# CH32H416RDU6-R0.net
KiCad netlist of a schematic drawn in Altium Designer
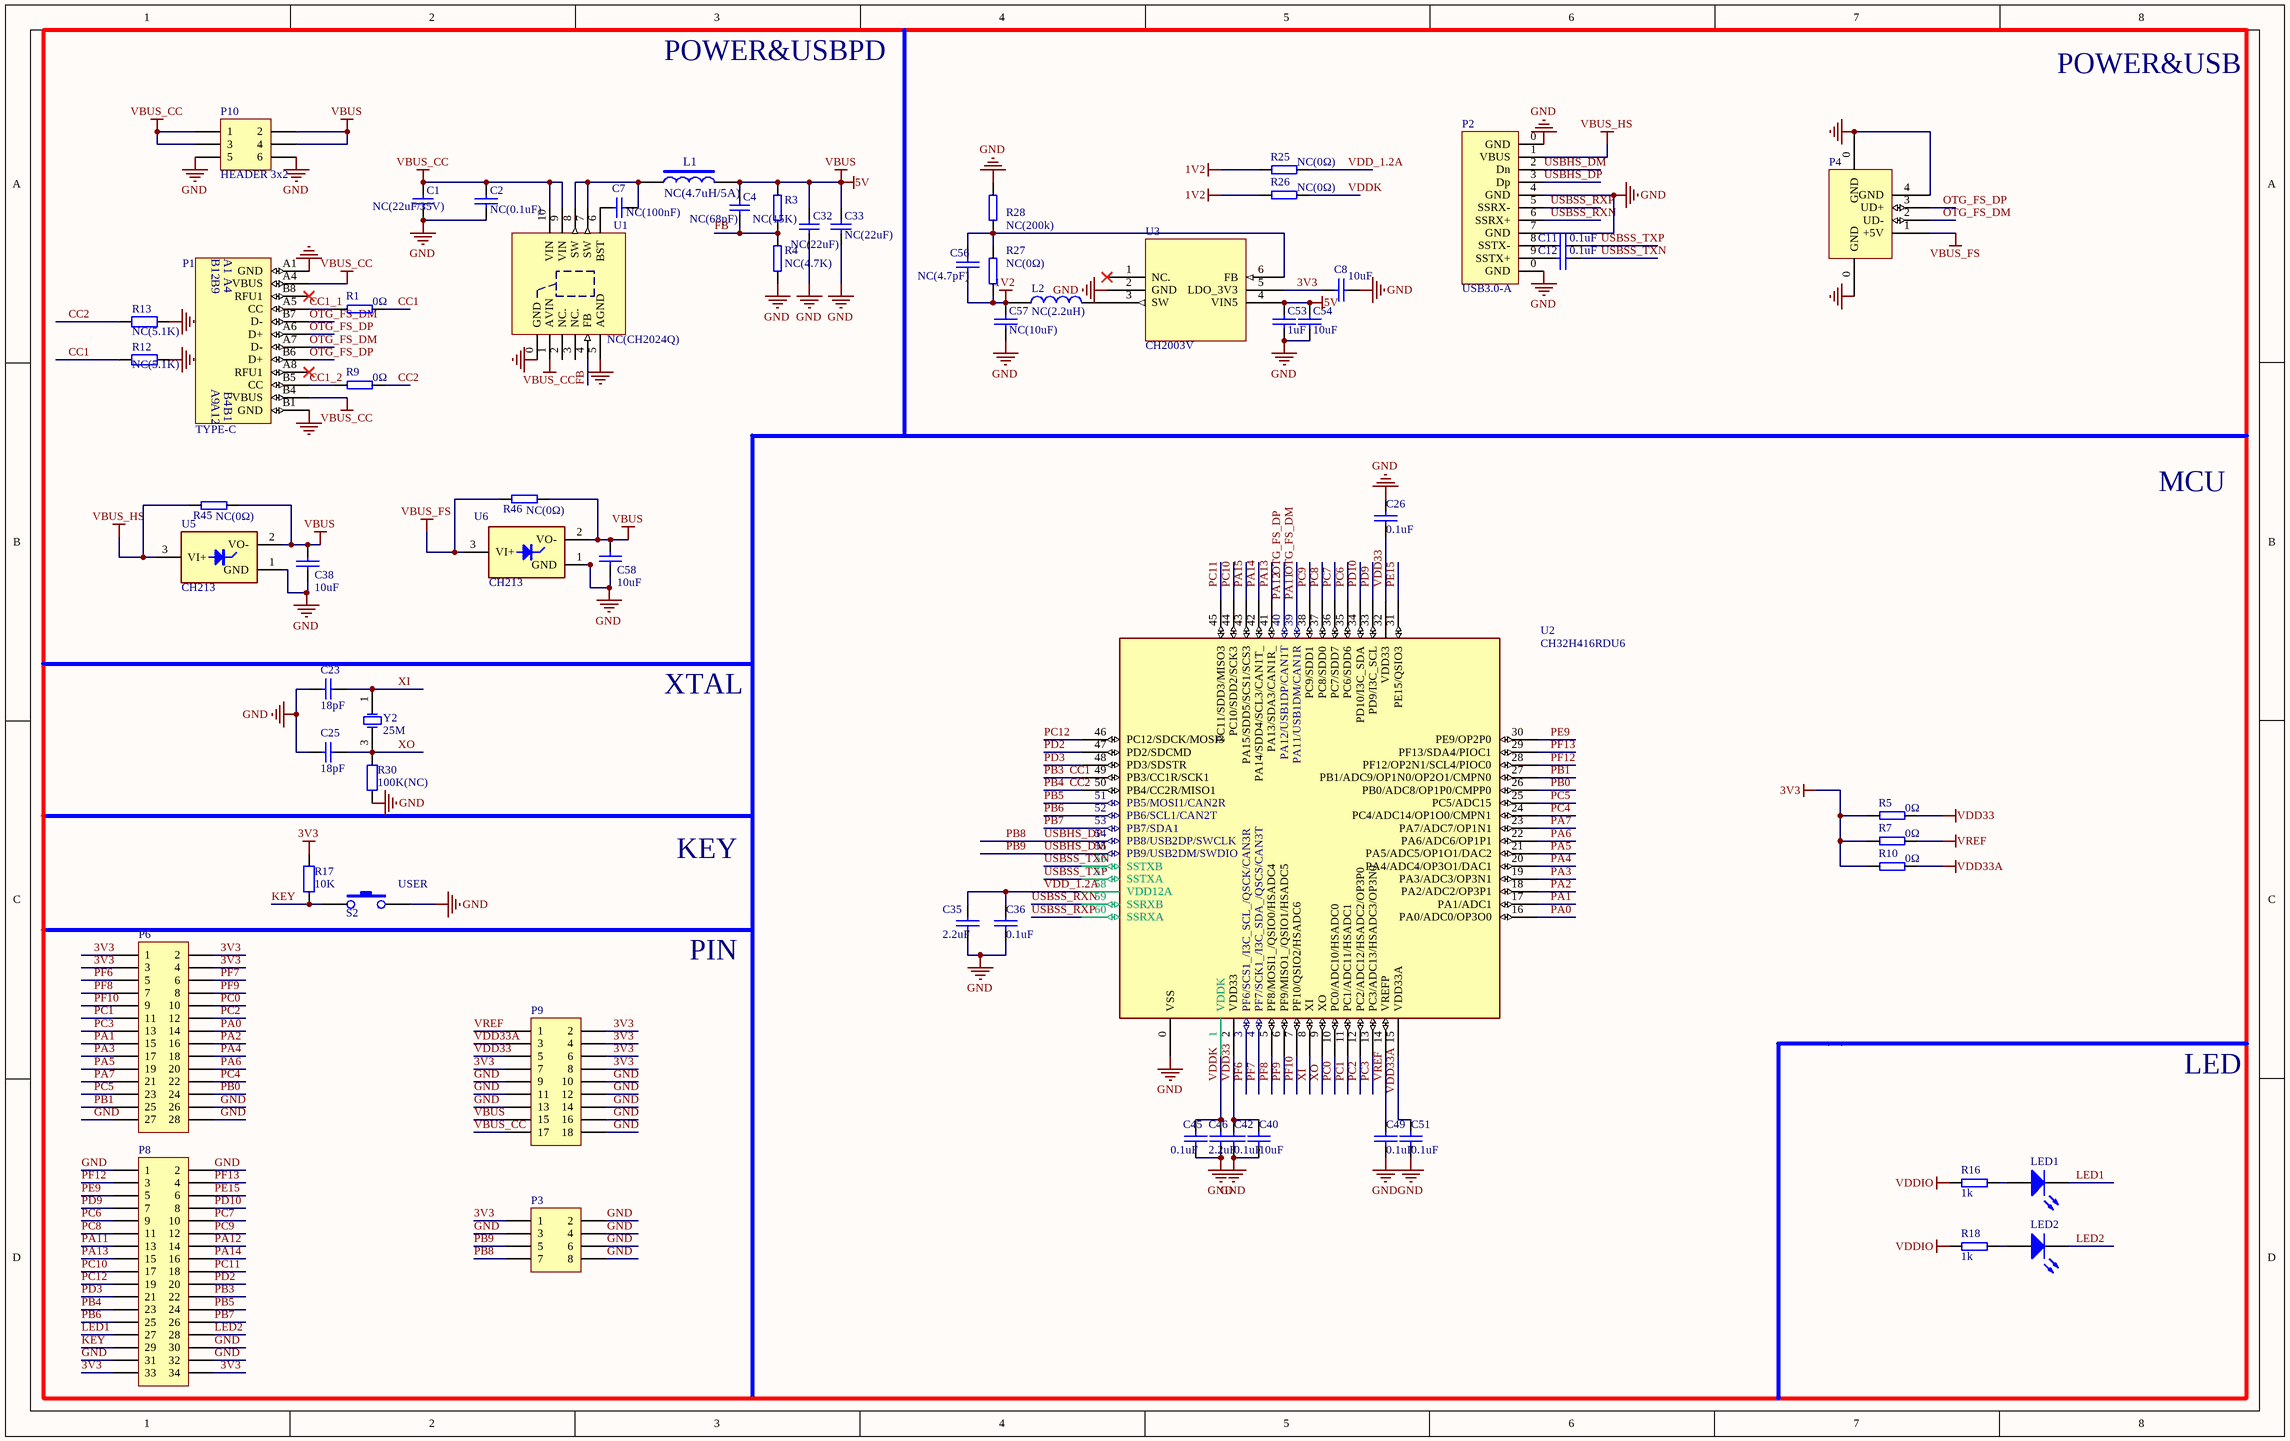
[diagram p0: CH32H416RDU6-R0.SchDoc]

(export (version "E")
  (design (tool "Eeschema 10.0.6"))
  (components
    (comp (ref "C1")
      (value "NC(22uF/35V)")
      (footprint "0805_C")
      (description "贴片电容")
      (libsource (lib "Miscellaneous Devices LC") (part "0603 100nF (104) 10% 50V"))
    )
    (comp (ref "C2")
      (value "NC(0.1uF)")
      (footprint "0402_C")
      (description "Capacitor")
      (libsource (lib "") (part "CAP_1"))
    )
    (comp (ref "C4")
      (value "NC(68pF)")
      (footprint "0402_C")
      (description "贴片电容")
      (libsource (lib "Miscellaneous Devices LC") (part "0603 100nF (104) 10% 50V"))
    )
    (comp (ref "C7")
      (value "NC(100nF)")
      (footprint "0603_C")
      (description "贴片电容")
      (libsource (lib "Miscellaneous Devices LC") (part "0603 1uF (105) 10% 50V"))
    )
    (comp (ref "C8")
      (value "10uF")
      (footprint "0603_C")
      (description "Capacitor")
      (libsource (lib "") (part "CAP_1"))
    )
    (comp (ref "C11")
      (value "0.1uF")
      (footprint "0402_C")
      (description "Capacitor")
      (libsource (lib "") (part "CAP_1"))
    )
    (comp (ref "C12")
      (value "0.1uF")
      (footprint "0402_C")
      (description "Capacitor")
      (libsource (lib "") (part "CAP_1"))
    )
    (comp (ref "C23")
      (value "18pF")
      (footprint "0402_C")
      (description "Capacitor")
      (libsource (lib "Miscellaneous Devices") (part "Cap"))
    )
    (comp (ref "C25")
      (value "18pF")
      (footprint "0402_C")
      (description "Capacitor")
      (libsource (lib "Miscellaneous Devices") (part "Cap"))
    )
    (comp (ref "C26")
      (value "0.1uF")
      (footprint "0402_C")
      (description "Capacitor")
      (libsource (lib "") (part "CAP_1"))
    )
    (comp (ref "C32")
      (value "NC(22uF)")
      (footprint "0805_C")
      (description "贴片电容")
      (libsource (lib "Miscellaneous Devices LC") (part "0603 100nF (104) 10% 50V"))
    )
    (comp (ref "C33")
      (value "NC(22uF)")
      (footprint "0805_C")
      (description "贴片电容")
      (libsource (lib "Miscellaneous Devices LC") (part "0603 100nF (104) 10% 50V"))
    )
    (comp (ref "C35")
      (value "2.2uF")
      (footprint "0402_C")
      (description "Capacitor")
      (libsource (lib "") (part "CAP_1"))
    )
    (comp (ref "C36")
      (value "0.1uF")
      (footprint "0402_C")
      (description "Capacitor")
      (libsource (lib "") (part "CAP_1"))
    )
    (comp (ref "C38")
      (value "10uF")
      (footprint "0603_C")
      (description "Capacitor")
      (libsource (lib "*") (part "CAP"))
    )
    (comp (ref "C40")
      (value "10uF")
      (footprint "0402_C")
      (description "Capacitor")
      (libsource (lib "") (part "CAP_1"))
    )
    (comp (ref "C42")
      (value "0.1uF")
      (footprint "0402_C")
      (description "Capacitor")
      (libsource (lib "") (part "CAP_1"))
    )
    (comp (ref "C45")
      (value "0.1uF")
      (footprint "0402_C")
      (description "Capacitor")
      (libsource (lib "") (part "CAP_1"))
    )
    (comp (ref "C46")
      (value "2.2uF")
      (footprint "0402_C")
      (description "Capacitor")
      (libsource (lib "") (part "CAP_1"))
    )
    (comp (ref "C49")
      (value "0.1uF")
      (footprint "0402_C")
      (description "Capacitor")
      (libsource (lib "") (part "CAP_1"))
    )
    (comp (ref "C51")
      (value "0.1uF")
      (footprint "0402_C")
      (description "Capacitor")
      (libsource (lib "") (part "CAP_1"))
    )
    (comp (ref "C53")
      (value "1uF")
      (footprint "0402_C")
      (description "Capacitor")
      (libsource (lib "") (part "CAP_2"))
    )
    (comp (ref "C54")
      (value "10uF")
      (footprint "0603_C")
      (description "Capacitor")
      (libsource (lib "") (part "CAP_1"))
    )
    (comp (ref "C56")
      (value "NC(4.7pF)")
      (footprint "0402_C")
      (description "Capacitor")
      (libsource (lib "") (part "CAP_2"))
    )
    (comp (ref "C57")
      (value "NC(10uF)")
      (footprint "0603_C")
      (description "Capacitor")
      (libsource (lib "") (part "CAP_1"))
    )
    (comp (ref "C58")
      (value "10uF")
      (footprint "0603_C")
      (description "Capacitor")
      (libsource (lib "*") (part "CAP"))
    )
    (comp (ref "L1")
      (value "NC(4.7uH/5A)")
      (footprint "SMD_6x6mm")
      (libsource (lib "wch_sch_others") (part "INDUCTOR"))
    )
    (comp (ref "L2") (value "NC(2.2uH)") (footprint "CD32") (libsource (lib "*") (part "INDUCTOR")))
    (comp (ref "LED1")
      (value "LED2  blue")
      (footprint "0603+")
      (description "Typical INFRARED GaAs LED")
      (fields (field (name "PUBLISHER") "Altium Limited"))
      (libsource (lib "Miscellaneous Devices") (part "LED0"))
    )
    (comp (ref "LED2")
      (value "LED1   blue")
      (footprint "0603+")
      (description "Typical INFRARED GaAs LED")
      (fields (field (name "PUBLISHER") "Altium Limited"))
      (libsource (lib "Miscellaneous Devices") (part "LED0"))
    )
    (comp (ref "P1")
      (value "TYPE-C")
      (footprint "TYPE-C-Receptacle-2.0")
      (libsource (lib "*") (part "TYPE-C1"))
    )
    (comp (ref "P2")
      (value "USB3.0-A")
      (footprint "USB3.0-A-Receptacle")
      (libsource (lib "wch_sch_others") (part "USB3.0-A"))
    )
    (comp (ref "P3")
      (value "HEADER 4x2")
      (footprint "MYPCB:IDC8-2.54mm")
      (description "Header, 4-Pin, Dual row")
      (libsource (lib "wch_sch_others") (part "HEADER 4x2"))
    )
    (comp (ref "P4")
      (value "USB_A")
      (footprint "USBAF")
      (description "USB Port")
      (libsource (lib "*") (part "USB"))
    )
    (comp (ref "P6")
      (value "HEADER 14x2")
      (footprint "MYPCB:IDC28-2.54MM")
      (description "Header, 14-Pin, Dual row")
      (libsource (lib "wch_sch_others") (part "HEADER 14x2"))
    )
    (comp (ref "P8")
      (value "HEADER 17x2")
      (footprint "MYPCB:IDC34-2.54MM")
      (description "Header, 17-Pin, Dual row")
      (libsource (lib "wch_sch_others") (part "HEADER 17x2"))
    )
    (comp (ref "P9")
      (value "HEADER 9x2")
      (footprint "MYPCB:IDC18-2.54MM")
      (description "Header, 9-Pin, Dual row")
      (libsource (lib "wch_sch_others") (part "HEADER 9x2"))
    )
    (comp (ref "P10")
      (value "HEADER 3x2")
      (footprint "MYPCB:IDC6-2.54mm")
      (description "Header, 3-Pin, Dual row")
      (libsource (lib "wch_sch_others") (part "HEADER 3x2"))
    )
    (comp (ref "R1") (value "0Ω") (footprint "0402") (libsource (lib "wch_sch_others") (part "RES")))
    (comp (ref "R3") (value "NC(15K)") (footprint "0402") (libsource (lib "wch_sch_others(1)") (part "RES")))
    (comp (ref "R4") (value "NC(4.7K)") (footprint "0402") (libsource (lib "wch_sch_others(1)") (part "RES")))
    (comp (ref "R5") (value "0Ω") (footprint "0402") (libsource (lib "wch_sch_others") (part "RES")))
    (comp (ref "R7") (value "0Ω") (footprint "0402") (libsource (lib "wch_sch_others") (part "RES")))
    (comp (ref "R9") (value "0Ω") (footprint "0402") (libsource (lib "wch_sch_others") (part "RES")))
    (comp (ref "R10") (value "0Ω") (footprint "0402") (libsource (lib "wch_sch_others") (part "RES")))
    (comp (ref "R12")
      (value "NC(5.1K)")
      (footprint "0402")
      (description "Resistor")
      (libsource (lib "") (part "Res2_1"))
    )
    (comp (ref "R13")
      (value "NC(5.1K)")
      (footprint "0402")
      (description "Resistor")
      (libsource (lib "") (part "Res2_1"))
    )
    (comp (ref "R16") (value "1k") (footprint "0402") (libsource (lib "wch_sch_others") (part "RES")))
    (comp (ref "R17")
      (value "10K")
      (footprint "0402")
      (description "Resistor")
      (libsource (lib "") (part "Res2_2"))
    )
    (comp (ref "R18") (value "1k") (footprint "0402") (libsource (lib "wch_sch_others") (part "RES")))
    (comp (ref "R25") (value "NC(0Ω)") (footprint "0402") (libsource (lib "wch_sch_others") (part "RES")))
    (comp (ref "R26") (value "NC(0Ω)") (footprint "0402") (libsource (lib "wch_sch_others") (part "RES")))
    (comp (ref "R27") (value "NC(0Ω)") (footprint "0402") (libsource (lib "wch_sch_others") (part "RES")))
    (comp (ref "R28") (value "NC(200k)") (footprint "0402") (libsource (lib "wch_sch_others") (part "RES")))
    (comp (ref "R30")
      (value "100K(NC)")
      (footprint "0402")
      (description "Resistor")
      (libsource (lib "Miscellaneous Devices") (part "Res2"))
    )
    (comp (ref "R45") (value "NC(0Ω)") (footprint "0402") (libsource (lib "") (part "RES_1")))
    (comp (ref "R46") (value "NC(0Ω)") (footprint "0402") (libsource (lib "") (part "RES_1")))
    (comp (ref "S2")
      (value "USER")
      (footprint "SMD_6.1x3.65x2.5mm-KEY")
      (libsource (lib "wch_sch_others") (part "KEY1"))
    )
    (comp (ref "U1")
      (value "NC(CH2024Q)")
      (footprint "DFN10_3X3")
      (description "Step-Down DC-DC Converter, 28V input, FB 1.2V, 3A output")
      (libsource (lib "DHXXXSCH") (part "CH2024Q"))
    )
    (comp (ref "U2")
      (value "CH32H416RDU6")
      (footprint "QFN60_6X6")
      (description "RISC-V FPU HD-MCU, 400MHz, USB3.0 & PD, SDMMC, QSPI, OPA, ADC, DAC")
      (libsource (lib "DHXXXSCH") (part "CH32H416RDU6"))
    )
    (comp (ref "U3")
      (value "CH2003V")
      (footprint "SOT-23-6")
      (description "Step-Down DC-DC Converter, 5V input, FB 0.6V, 800mA output, with LDO 3.3V * 200mA")
      (libsource (lib "DHXXXSCH") (part "CH2003K"))
    )
    (comp (ref "U5")
      (value "CH213")
      (footprint "SOT-23-3")
      (description "Ideal Diode 5V*1A")
      (libsource (lib "CHXXX") (part "CH213E"))
    )
    (comp (ref "U6")
      (value "CH213")
      (footprint "SOT-23-3")
      (description "Ideal Diode 5V*1A")
      (libsource (lib "CHXXX") (part "CH213E"))
    )
    (comp (ref "Y2")
      (value "25M")
      (footprint "XT3225")
      (description "Crystal Oscillator")
      (fields (field (name "PUBLISHER") "Altium Limited"))
      (libsource (lib "Miscellaneous Devices") (part "XTAL"))
    )
  )
  (nets
    (net (code "2") (name "/CC1") (class "Default")
      (node (ref "P8") (pin "22") (pinfunction "22_22") (pintype "passive"))
      (node (ref "R1") (pin "1") (pintype "passive"))
      (node (ref "R12") (pin "1") (pinfunction "1_1") (pintype "passive"))
      (node (ref "U2") (pin "49") (pinfunction "PB3/CC1R/SCK1_49") (pintype "bidirectional"))
    )
    (net (code "3") (name "/CC1_1") (class "Default")
      (node (ref "P1") (pin "A5") (pinfunction "CC_A5") (pintype "bidirectional"))
      (node (ref "R1") (pin "2") (pintype "passive"))
    )
    (net (code "4") (name "/CC1_2") (class "Default")
      (node (ref "P1") (pin "B5") (pinfunction "CC_B5") (pintype "bidirectional"))
      (node (ref "R9") (pin "2") (pintype "passive"))
    )
    (net (code "5") (name "/CC2") (class "Default")
      (node (ref "P8") (pin "23") (pinfunction "23_23") (pintype "passive"))
      (node (ref "R13") (pin "1") (pinfunction "1_1") (pintype "passive"))
      (node (ref "R9") (pin "1") (pintype "passive"))
      (node (ref "U2") (pin "50") (pinfunction "PB4/CC2R/MISO1_50") (pintype "bidirectional"))
    )
    (net (code "6") (name "/FB") (class "Default")
      (node (ref "C4") (pin "2") (pinfunction "2_2") (pintype "passive"))
      (node (ref "R3") (pin "1") (pintype "passive"))
      (node (ref "R4") (pin "2") (pintype "passive"))
      (node (ref "U1") (pin "4") (pinfunction "FB_4") (pintype "input"))
    )
    (net (code "7") (name "/KEY") (class "Default")
      (node (ref "P8") (pin "29") (pinfunction "29_29") (pintype "passive"))
      (node (ref "R17") (pin "2") (pinfunction "2_2") (pintype "passive"))
      (node (ref "S2") (pin "1") (pinfunction "1_1") (pintype "passive"))
    )
    (net (code "8") (name "/LED1") (class "Default")
      (node (ref "LED1") (pin "2") (pinfunction "K_2") (pintype "passive"))
      (node (ref "P8") (pin "27") (pinfunction "27_27") (pintype "passive"))
    )
    (net (code "9") (name "/LED2") (class "Default")
      (node (ref "LED2") (pin "2") (pinfunction "K_2") (pintype "passive"))
      (node (ref "P8") (pin "28") (pinfunction "28_28") (pintype "passive"))
    )
    (net (code "10") (name "/OTG_FS_DM") (class "Default")
      (node (ref "P1") (pin "A7") (pinfunction "D-_A7") (pintype "bidirectional"))
      (node (ref "P1") (pin "B7") (pinfunction "D-_B7") (pintype "bidirectional"))
      (node (ref "P4") (pin "2") (pinfunction "UD-_2") (pintype "bidirectional"))
      (node (ref "P8") (pin "13") (pinfunction "13_13") (pintype "passive"))
      (node (ref "U2") (pin "39") (pinfunction "PA11/USB1DM/CAN1R_39") (pintype "bidirectional"))
    )
    (net (code "11") (name "/OTG_FS_DP") (class "Default")
      (node (ref "P1") (pin "A6") (pinfunction "D+_A6") (pintype "bidirectional"))
      (node (ref "P1") (pin "B6") (pinfunction "D+_B6") (pintype "bidirectional"))
      (node (ref "P4") (pin "3") (pinfunction "UD+_3") (pintype "bidirectional"))
      (node (ref "P8") (pin "14") (pinfunction "14_14") (pintype "passive"))
      (node (ref "U2") (pin "40") (pinfunction "PA12/USB1DP/CAN1T_40") (pintype "bidirectional"))
    )
    (net (code "12") (name "/PA0") (class "Default")
      (node (ref "P6") (pin "14") (pinfunction "14_14") (pintype "passive"))
      (node (ref "U2") (pin "16") (pinfunction "PA0/ADC0/OP3O0_16") (pintype "bidirectional"))
    )
    (net (code "13") (name "/PA1") (class "Default")
      (node (ref "P6") (pin "15") (pinfunction "15_15") (pintype "passive"))
      (node (ref "U2") (pin "17") (pinfunction "PA1/ADC1_17") (pintype "bidirectional"))
    )
    (net (code "14") (name "/PA2") (class "Default")
      (node (ref "P6") (pin "16") (pinfunction "16_16") (pintype "passive"))
      (node (ref "U2") (pin "18") (pinfunction "PA2/ADC2/OP3P1_18") (pintype "bidirectional"))
    )
    (net (code "15") (name "/PA3") (class "Default")
      (node (ref "P6") (pin "17") (pinfunction "17_17") (pintype "passive"))
      (node (ref "U2") (pin "19") (pinfunction "PA3/ADC3/OP3N1_19") (pintype "bidirectional"))
    )
    (net (code "16") (name "/PA4") (class "Default")
      (node (ref "P6") (pin "18") (pinfunction "18_18") (pintype "passive"))
      (node (ref "U2") (pin "20") (pinfunction "PA4/ADC4/OP3O1/DAC1_20") (pintype "bidirectional"))
    )
    (net (code "17") (name "/PA5") (class "Default")
      (node (ref "P6") (pin "19") (pinfunction "19_19") (pintype "passive"))
      (node (ref "U2") (pin "21") (pinfunction "PA5/ADC5/OP1O1/DAC2_21") (pintype "bidirectional"))
    )
    (net (code "18") (name "/PA6") (class "Default")
      (node (ref "P6") (pin "20") (pinfunction "20_20") (pintype "passive"))
      (node (ref "U2") (pin "22") (pinfunction "PA6/ADC6/OP1P1_22") (pintype "bidirectional"))
    )
    (net (code "19") (name "/PA7") (class "Default")
      (node (ref "P6") (pin "21") (pinfunction "21_21") (pintype "passive"))
      (node (ref "U2") (pin "23") (pinfunction "PA7/ADC7/OP1N1_23") (pintype "bidirectional"))
    )
    (net (code "20") (name "/PA13") (class "Default")
      (node (ref "P8") (pin "15") (pinfunction "15_15") (pintype "passive"))
      (node (ref "U2") (pin "41") (pinfunction "PA13/SDA3/CAN1R__41") (pintype "bidirectional"))
    )
    (net (code "21") (name "/PA14") (class "Default")
      (node (ref "P8") (pin "16") (pinfunction "16_16") (pintype "passive"))
      (node (ref "U2") (pin "42") (pinfunction "PA14/SDD4/SCL3/CAN1T__42") (pintype "bidirectional"))
    )
    (net (code "22") (name "/PA15") (class "Default")
      (node (ref "U2") (pin "43") (pinfunction "PA15/SDD5/SCS1/SCS3_43") (pintype "bidirectional"))
    )
    (net (code "23") (name "/PB0") (class "Default")
      (node (ref "P6") (pin "24") (pinfunction "24_24") (pintype "passive"))
      (node (ref "U2") (pin "26") (pinfunction "PB0/ADC8/OP1P0/CMPP0_26") (pintype "bidirectional"))
    )
    (net (code "24") (name "/PB1") (class "Default")
      (node (ref "P6") (pin "25") (pinfunction "25_25") (pintype "passive"))
      (node (ref "U2") (pin "27") (pinfunction "PB1/ADC9/OP1N0/OP2O1/CMPN0_27") (pintype "bidirectional"))
    )
    (net (code "25") (name "/PB5") (class "Default")
      (node (ref "P8") (pin "24") (pinfunction "24_24") (pintype "passive"))
      (node (ref "U2") (pin "51") (pinfunction "PB5/MOSI1/CAN2R_51") (pintype "bidirectional"))
    )
    (net (code "26") (name "/PB6") (class "Default")
      (node (ref "P8") (pin "25") (pinfunction "25_25") (pintype "passive"))
      (node (ref "U2") (pin "52") (pinfunction "PB6/SCL1/CAN2T_52") (pintype "bidirectional"))
    )
    (net (code "27") (name "/PB7") (class "Default")
      (node (ref "P8") (pin "26") (pinfunction "26_26") (pintype "passive"))
      (node (ref "U2") (pin "53") (pinfunction "PB7/SDA1_53") (pintype "bidirectional"))
    )
    (net (code "28") (name "/PB8") (class "Default")
      (node (ref "P2") (pin "3") (pinfunction "Dp_3") (pintype "passive"))
      (node (ref "P3") (pin "7") (pinfunction "7_7") (pintype "passive"))
      (node (ref "U2") (pin "54") (pinfunction "PB8/USB2DP/SWCLK_54") (pintype "bidirectional"))
    )
    (net (code "29") (name "/PB9") (class "Default")
      (node (ref "P2") (pin "2") (pinfunction "Dn_2") (pintype "passive"))
      (node (ref "P3") (pin "5") (pinfunction "5_5") (pintype "passive"))
      (node (ref "U2") (pin "55") (pinfunction "PB9/USB2DM/SWDIO_55") (pintype "bidirectional"))
    )
    (net (code "30") (name "/PC0") (class "Default")
      (node (ref "P6") (pin "10") (pinfunction "10_10") (pintype "passive"))
      (node (ref "U2") (pin "10") (pinfunction "PC0/ADC10/HSADC0_10") (pintype "bidirectional"))
    )
    (net (code "31") (name "/PC1") (class "Default")
      (node (ref "P6") (pin "11") (pinfunction "11_11") (pintype "passive"))
      (node (ref "U2") (pin "11") (pinfunction "PC1/ADC11/HSADC1_11") (pintype "bidirectional"))
    )
    (net (code "32") (name "/PC2") (class "Default")
      (node (ref "P6") (pin "12") (pinfunction "12_12") (pintype "passive"))
      (node (ref "U2") (pin "12") (pinfunction "PC2/ADC12/HSADC2/OP3P0_12") (pintype "bidirectional"))
    )
    (net (code "33") (name "/PC3") (class "Default")
      (node (ref "P6") (pin "13") (pinfunction "13_13") (pintype "passive"))
      (node (ref "U2") (pin "13") (pinfunction "PC3/ADC13/HSADC3/OP3N0_13") (pintype "bidirectional"))
    )
    (net (code "34") (name "/PC4") (class "Default")
      (node (ref "P6") (pin "22") (pinfunction "22_22") (pintype "passive"))
      (node (ref "U2") (pin "24") (pinfunction "PC4/ADC14/OP1O0/CMPN1_24") (pintype "bidirectional"))
    )
    (net (code "35") (name "/PC5") (class "Default")
      (node (ref "P6") (pin "23") (pinfunction "23_23") (pintype "passive"))
      (node (ref "U2") (pin "25") (pinfunction "PC5/ADC15_25") (pintype "bidirectional"))
    )
    (net (code "36") (name "/PC6") (class "Default")
      (node (ref "P8") (pin "9") (pinfunction "9_9") (pintype "passive"))
      (node (ref "U2") (pin "35") (pinfunction "PC6/SDD6_35") (pintype "bidirectional"))
    )
    (net (code "37") (name "/PC7") (class "Default")
      (node (ref "P8") (pin "10") (pinfunction "10_10") (pintype "passive"))
      (node (ref "U2") (pin "36") (pinfunction "PC7/SDD7_36") (pintype "bidirectional"))
    )
    (net (code "38") (name "/PC8") (class "Default")
      (node (ref "P8") (pin "11") (pinfunction "11_11") (pintype "passive"))
      (node (ref "U2") (pin "37") (pinfunction "PC8/SDD0_37") (pintype "bidirectional"))
    )
    (net (code "39") (name "/PC9") (class "Default")
      (node (ref "P8") (pin "12") (pinfunction "12_12") (pintype "passive"))
      (node (ref "U2") (pin "38") (pinfunction "PC9/SDD1_38") (pintype "bidirectional"))
    )
    (net (code "40") (name "/PC10") (class "Default")
      (node (ref "P8") (pin "17") (pinfunction "17_17") (pintype "passive"))
      (node (ref "U2") (pin "44") (pinfunction "PC10/SDD2/SCK3_44") (pintype "bidirectional"))
    )
    (net (code "41") (name "/PC11") (class "Default")
      (node (ref "P8") (pin "18") (pinfunction "18_18") (pintype "passive"))
      (node (ref "U2") (pin "45") (pinfunction "PC11/SDD3/MISO3_45") (pintype "bidirectional"))
    )
    (net (code "42") (name "/PC12") (class "Default")
      (node (ref "P8") (pin "19") (pinfunction "19_19") (pintype "passive"))
      (node (ref "U2") (pin "46") (pinfunction "PC12/SDCK/MOSI3_46") (pintype "bidirectional"))
    )
    (net (code "43") (name "/PD2") (class "Default")
      (node (ref "P8") (pin "20") (pinfunction "20_20") (pintype "passive"))
      (node (ref "U2") (pin "47") (pinfunction "PD2/SDCMD_47") (pintype "bidirectional"))
    )
    (net (code "44") (name "/PD3") (class "Default")
      (node (ref "P8") (pin "21") (pinfunction "21_21") (pintype "passive"))
      (node (ref "U2") (pin "48") (pinfunction "PD3/SDSTR_48") (pintype "bidirectional"))
    )
    (net (code "45") (name "/PD9") (class "Default")
      (node (ref "P8") (pin "7") (pinfunction "7_7") (pintype "passive"))
      (node (ref "U2") (pin "33") (pinfunction "PD9/I3C_SCL_33") (pintype "bidirectional"))
    )
    (net (code "46") (name "/PD10") (class "Default")
      (node (ref "P8") (pin "8") (pinfunction "8_8") (pintype "passive"))
      (node (ref "U2") (pin "34") (pinfunction "PD10/I3C_SDA_34") (pintype "bidirectional"))
    )
    (net (code "47") (name "/PE9") (class "Default")
      (node (ref "P8") (pin "5") (pinfunction "5_5") (pintype "passive"))
      (node (ref "U2") (pin "30") (pinfunction "PE9/OP2P0_30") (pintype "bidirectional"))
    )
    (net (code "48") (name "/PE15") (class "Default")
      (node (ref "P8") (pin "6") (pinfunction "6_6") (pintype "passive"))
      (node (ref "U2") (pin "31") (pinfunction "PE15/QSIO3_31") (pintype "bidirectional"))
    )
    (net (code "49") (name "/PF6") (class "Default")
      (node (ref "P6") (pin "5") (pinfunction "5_5") (pintype "passive"))
      (node (ref "U2") (pin "3") (pinfunction "PF6/SCS1_/I3C_SCL_/QSCK/CAN3R_3") (pintype "bidirectional"))
    )
    (net (code "50") (name "/PF7") (class "Default")
      (node (ref "P6") (pin "6") (pinfunction "6_6") (pintype "passive"))
      (node (ref "U2") (pin "4") (pinfunction "PF7/SCK1_/I3C_SDA_/QSCS/CAN3T_4") (pintype "bidirectional"))
    )
    (net (code "51") (name "/PF8") (class "Default")
      (node (ref "P6") (pin "7") (pinfunction "7_7") (pintype "passive"))
      (node (ref "U2") (pin "5") (pinfunction "PF8/MOSI1_/QSIO0/HSADC4_5") (pintype "bidirectional"))
    )
    (net (code "52") (name "/PF9") (class "Default")
      (node (ref "P6") (pin "8") (pinfunction "8_8") (pintype "passive"))
      (node (ref "U2") (pin "6") (pinfunction "PF9/MISO1_/QSIO1/HSADC5_6") (pintype "bidirectional"))
    )
    (net (code "53") (name "/PF10") (class "Default")
      (node (ref "P6") (pin "9") (pinfunction "9_9") (pintype "passive"))
      (node (ref "U2") (pin "7") (pinfunction "PF10/QSIO2/HSADC6_7") (pintype "bidirectional"))
    )
    (net (code "54") (name "/PF12") (class "Default")
      (node (ref "P8") (pin "3") (pinfunction "3_3") (pintype "passive"))
      (node (ref "U2") (pin "28") (pinfunction "PF12/OP2N1/SCL4/PIOC0_28") (pintype "bidirectional"))
    )
    (net (code "55") (name "/PF13") (class "Default")
      (node (ref "P8") (pin "4") (pinfunction "4_4") (pintype "passive"))
      (node (ref "U2") (pin "29") (pinfunction "PF13/SDA4/PIOC1_29") (pintype "bidirectional"))
    )
    (net (code "56") (name "/USBSS_RXN") (class "Default")
      (node (ref "P2") (pin "6") (pinfunction "SSRX+_6") (pintype "passive"))
      (node (ref "U2") (pin "59") (pinfunction "SSRXB_59") (pintype "bidirectional"))
    )
    (net (code "57") (name "/USBSS_RXP") (class "Default")
      (node (ref "P2") (pin "5") (pinfunction "SSRX-_5") (pintype "passive"))
      (node (ref "U2") (pin "60") (pinfunction "SSRXA_60") (pintype "bidirectional"))
    )
    (net (code "58") (name "/USBSS_TXN") (class "Default")
      (node (ref "C12") (pin "2") (pinfunction "2_2") (pintype "passive"))
      (node (ref "U2") (pin "56") (pinfunction "SSTXB_56") (pintype "bidirectional"))
    )
    (net (code "59") (name "/USBSS_TXP") (class "Default")
      (node (ref "C11") (pin "2") (pinfunction "2_2") (pintype "passive"))
      (node (ref "U2") (pin "57") (pinfunction "SSTXA_57") (pintype "bidirectional"))
    )
    (net (code "60") (name "/VDDK") (class "Default")
      (node (ref "C45") (pin "2") (pinfunction "2_2") (pintype "passive"))
      (node (ref "C46") (pin "1") (pinfunction "1_1") (pintype "passive"))
      (node (ref "R26") (pin "1") (pintype "passive"))
      (node (ref "U2") (pin "1") (pinfunction "VDDK_1") (pintype "power_in"))
    )
    (net (code "61") (name "/VDD_1.2A") (class "Default")
      (node (ref "C35") (pin "2") (pinfunction "2_2") (pintype "passive"))
      (node (ref "C36") (pin "2") (pinfunction "2_2") (pintype "passive"))
      (node (ref "R25") (pin "1") (pintype "passive"))
      (node (ref "U2") (pin "58") (pinfunction "VDD12A_58") (pintype "power_in"))
    )
    (net (code "62") (name "/XI") (class "Default")
      (node (ref "C23") (pin "2") (pinfunction "2_2") (pintype "passive"))
      (node (ref "U2") (pin "8") (pinfunction "XI_8") (pintype "bidirectional"))
      (node (ref "Y2") (pin "1") (pinfunction "OSC1_1") (pintype "passive"))
    )
    (net (code "63") (name "/XO") (class "Default")
      (node (ref "C25") (pin "2") (pinfunction "2_2") (pintype "passive"))
      (node (ref "R30") (pin "2") (pinfunction "2_2") (pintype "passive"))
      (node (ref "U2") (pin "9") (pinfunction "XO_9") (pintype "bidirectional"))
      (node (ref "Y2") (pin "3") (pinfunction "OSC2_3") (pintype "passive"))
    )
    (net (code "64") (name "1V2") (class "Default")
      (node (ref "C56") (pin "1") (pinfunction "1_1") (pintype "passive"))
      (node (ref "C57") (pin "2") (pinfunction "2_2") (pintype "passive"))
      (node (ref "L2") (pin "2") (pinfunction "2_2") (pintype "passive"))
      (node (ref "R25") (pin "2") (pintype "passive"))
      (node (ref "R26") (pin "2") (pintype "passive"))
      (node (ref "R27") (pin "1") (pintype "passive"))
    )
    (net (code "65") (name "3V3") (class "Default")
      (node (ref "C8") (pin "2") (pinfunction "2_2") (pintype "passive"))
      (node (ref "P3") (pin "1") (pinfunction "1_1") (pintype "passive"))
      (node (ref "P6") (pin "1") (pinfunction "1_1") (pintype "passive"))
      (node (ref "P6") (pin "2") (pinfunction "2_2") (pintype "passive"))
      (node (ref "P6") (pin "3") (pinfunction "3_3") (pintype "passive"))
      (node (ref "P6") (pin "4") (pinfunction "4_4") (pintype "passive"))
      (node (ref "P8") (pin "33") (pinfunction "33_33") (pintype "passive"))
      (node (ref "P8") (pin "34") (pinfunction "34_34") (pintype "passive"))
      (node (ref "P9") (pin "2") (pinfunction "2_2") (pintype "passive"))
      (node (ref "P9") (pin "4") (pinfunction "4_4") (pintype "passive"))
      (node (ref "P9") (pin "6") (pinfunction "6_6") (pintype "passive"))
      (node (ref "P9") (pin "7") (pinfunction "7_7") (pintype "passive"))
      (node (ref "P9") (pin "8") (pinfunction "8_8") (pintype "passive"))
      (node (ref "R10") (pin "2") (pintype "passive"))
      (node (ref "R17") (pin "1") (pinfunction "1_1") (pintype "passive"))
      (node (ref "R5") (pin "2") (pintype "passive"))
      (node (ref "R7") (pin "2") (pintype "passive"))
      (node (ref "U3") (pin "5") (pinfunction "LDO_3V3_5") (pintype "power_in"))
    )
    (net (code "66") (name "5V") (class "Default")
      (node (ref "C32") (pin "2") (pinfunction "2_2") (pintype "passive"))
      (node (ref "C33") (pin "2") (pinfunction "2_2") (pintype "passive"))
      (node (ref "C38") (pin "1") (pinfunction "1_1") (pintype "passive"))
      (node (ref "C4") (pin "1") (pinfunction "1_1") (pintype "passive"))
      (node (ref "C53") (pin "2") (pinfunction "2_2") (pintype "passive"))
      (node (ref "C54") (pin "2") (pinfunction "2_2") (pintype "passive"))
      (node (ref "C58") (pin "1") (pinfunction "1_1") (pintype "passive"))
      (node (ref "L1") (pin "2") (pinfunction "2_2") (pintype "passive"))
      (node (ref "P10") (pin "2") (pinfunction "2_2") (pintype "passive"))
      (node (ref "P10") (pin "4") (pinfunction "4_4") (pintype "passive"))
      (node (ref "P9") (pin "15") (pinfunction "15_15") (pintype "passive"))
      (node (ref "R3") (pin "2") (pintype "passive"))
      (node (ref "R45") (pin "1") (pintype "passive"))
      (node (ref "R46") (pin "1") (pintype "passive"))
      (node (ref "U3") (pin "4") (pinfunction "VIN5_4") (pintype "power_in"))
      (node (ref "U5") (pin "2") (pinfunction "VO-_2") (pintype "power_in"))
      (node (ref "U6") (pin "2") (pinfunction "VO-_2") (pintype "power_in"))
    )
    (net (code "67") (name "GND") (class "Default")
      (node (ref "C1") (pin "1") (pinfunction "1_1") (pintype "passive"))
      (node (ref "C2") (pin "1") (pinfunction "1_1") (pintype "passive"))
      (node (ref "C23") (pin "1") (pinfunction "1_1") (pintype "passive"))
      (node (ref "C25") (pin "1") (pinfunction "1_1") (pintype "passive"))
      (node (ref "C26") (pin "2") (pinfunction "2_2") (pintype "passive"))
      (node (ref "C32") (pin "1") (pinfunction "1_1") (pintype "passive"))
      (node (ref "C33") (pin "1") (pinfunction "1_1") (pintype "passive"))
      (node (ref "C35") (pin "1") (pinfunction "1_1") (pintype "passive"))
      (node (ref "C36") (pin "1") (pinfunction "1_1") (pintype "passive"))
      (node (ref "C38") (pin "2") (pinfunction "2_2") (pintype "passive"))
      (node (ref "C40") (pin "1") (pinfunction "1_1") (pintype "passive"))
      (node (ref "C42") (pin "1") (pinfunction "1_1") (pintype "passive"))
      (node (ref "C45") (pin "1") (pinfunction "1_1") (pintype "passive"))
      (node (ref "C46") (pin "2") (pinfunction "2_2") (pintype "passive"))
      (node (ref "C49") (pin "1") (pinfunction "1_1") (pintype "passive"))
      (node (ref "C51") (pin "1") (pinfunction "1_1") (pintype "passive"))
      (node (ref "C53") (pin "1") (pinfunction "1_1") (pintype "passive"))
      (node (ref "C54") (pin "1") (pinfunction "1_1") (pintype "passive"))
      (node (ref "C57") (pin "1") (pinfunction "1_1") (pintype "passive"))
      (node (ref "C58") (pin "2") (pinfunction "2_2") (pintype "passive"))
      (node (ref "C8") (pin "1") (pinfunction "1_1") (pintype "passive"))
      (node (ref "P1") (pin "A1") (pinfunction "GND_A1") (pintype "bidirectional"))
      (node (ref "P1") (pin "B1") (pinfunction "GND_B1") (pintype "bidirectional"))
      (node (ref "P10") (pin "5") (pinfunction "5_5") (pintype "passive"))
      (node (ref "P10") (pin "6") (pinfunction "6_6") (pintype "passive"))
      (node (ref "P2") (pin "0") (pinfunction "GND_0") (pintype "passive"))
      (node (ref "P2") (pin "4") (pinfunction "GND_4") (pintype "passive"))
      (node (ref "P2") (pin "7") (pinfunction "GND_7") (pintype "passive"))
      (node (ref "P3") (pin "2") (pinfunction "2_2") (pintype "passive"))
      (node (ref "P3") (pin "3") (pinfunction "3_3") (pintype "passive"))
      (node (ref "P3") (pin "4") (pinfunction "4_4") (pintype "passive"))
      (node (ref "P3") (pin "6") (pinfunction "6_6") (pintype "passive"))
      (node (ref "P3") (pin "8") (pinfunction "8_8") (pintype "passive"))
      (node (ref "P4") (pin "0") (pinfunction "GND_0") (pintype "power_in"))
      (node (ref "P4") (pin "4") (pinfunction "GND_4") (pintype "power_in"))
      (node (ref "P6") (pin "26") (pinfunction "26_26") (pintype "passive"))
      (node (ref "P6") (pin "27") (pinfunction "27_27") (pintype "passive"))
      (node (ref "P6") (pin "28") (pinfunction "28_28") (pintype "passive"))
      (node (ref "P8") (pin "1") (pinfunction "1_1") (pintype "passive"))
      (node (ref "P8") (pin "2") (pinfunction "2_2") (pintype "passive"))
      (node (ref "P8") (pin "30") (pinfunction "30_30") (pintype "passive"))
      (node (ref "P8") (pin "31") (pinfunction "31_31") (pintype "passive"))
      (node (ref "P8") (pin "32") (pinfunction "32_32") (pintype "passive"))
      (node (ref "P9") (pin "10") (pinfunction "10_10") (pintype "passive"))
      (node (ref "P9") (pin "11") (pinfunction "11_11") (pintype "passive"))
      (node (ref "P9") (pin "12") (pinfunction "12_12") (pintype "passive"))
      (node (ref "P9") (pin "13") (pinfunction "13_13") (pintype "passive"))
      (node (ref "P9") (pin "14") (pinfunction "14_14") (pintype "passive"))
      (node (ref "P9") (pin "16") (pinfunction "16_16") (pintype "passive"))
      (node (ref "P9") (pin "18") (pinfunction "18_18") (pintype "passive"))
      (node (ref "P9") (pin "9") (pinfunction "9_9") (pintype "passive"))
      (node (ref "R12") (pin "2") (pinfunction "2_2") (pintype "passive"))
      (node (ref "R13") (pin "2") (pinfunction "2_2") (pintype "passive"))
      (node (ref "R28") (pin "2") (pintype "passive"))
      (node (ref "R30") (pin "1") (pinfunction "1_1") (pintype "passive"))
      (node (ref "R4") (pin "1") (pintype "passive"))
      (node (ref "S2") (pin "2") (pinfunction "2_2") (pintype "passive"))
      (node (ref "U1") (pin "0") (pinfunction "GND_0") (pintype "power_in"))
      (node (ref "U1") (pin "5") (pinfunction "AGND_5") (pintype "power_in"))
      (node (ref "U2") (pin "0") (pinfunction "VSS_0") (pintype "power_in"))
      (node (ref "U3") (pin "2") (pinfunction "GND_2") (pintype "power_in"))
      (node (ref "U5") (pin "1") (pinfunction "GND_1") (pintype "power_in"))
      (node (ref "U6") (pin "1") (pinfunction "GND_1") (pintype "power_in"))
    )
    (net (code "68") (name "Net-(C7-Pad2)") (class "Default")
      (node (ref "C7") (pin "2") (pinfunction "2_2") (pintype "passive"))
      (node (ref "L1") (pin "1") (pinfunction "1_1") (pintype "passive"))
      (node (ref "U1") (pin "7") (pinfunction "SW_7") (pintype "output"))
      (node (ref "U1") (pin "8") (pinfunction "SW_8") (pintype "output"))
    )
    (net (code "69") (name "Net-(LED1-A)") (class "Default")
      (node (ref "LED1") (pin "1") (pinfunction "A_1") (pintype "passive"))
      (node (ref "R16") (pin "2") (pintype "passive"))
    )
    (net (code "70") (name "Net-(LED2-A)") (class "Default")
      (node (ref "LED2") (pin "1") (pinfunction "A_1") (pintype "passive"))
      (node (ref "R18") (pin "2") (pintype "passive"))
    )
    (net (code "71") (name "Net-(P2-SSTX+)") (class "Default")
      (node (ref "C12") (pin "1") (pinfunction "1_1") (pintype "passive"))
      (node (ref "P2") (pin "9") (pinfunction "SSTX+_9") (pintype "passive"))
    )
    (net (code "72") (name "Net-(P2-SSTX-)") (class "Default")
      (node (ref "C11") (pin "1") (pinfunction "1_1") (pintype "passive"))
      (node (ref "P2") (pin "8") (pinfunction "SSTX-_8") (pintype "passive"))
    )
    (net (code "73") (name "Net-(U1-BST)") (class "Default")
      (node (ref "C7") (pin "1") (pinfunction "1_1") (pintype "passive"))
      (node (ref "U1") (pin "6") (pinfunction "BST_6") (pintype "power_in"))
    )
    (net (code "74") (name "Net-(U3-FB)") (class "Default")
      (node (ref "C56") (pin "2") (pinfunction "2_2") (pintype "passive"))
      (node (ref "R27") (pin "2") (pintype "passive"))
      (node (ref "R28") (pin "1") (pintype "passive"))
      (node (ref "U3") (pin "6") (pinfunction "FB_6") (pintype "input"))
    )
    (net (code "75") (name "Net-(U3-SW)") (class "Default")
      (node (ref "L2") (pin "1") (pinfunction "1_1") (pintype "passive"))
      (node (ref "U3") (pin "3") (pinfunction "SW_3") (pintype "output"))
    )
    (net (code "76") (name "VBUS_CC") (class "Default")
      (node (ref "C1") (pin "2") (pinfunction "2_2") (pintype "passive"))
      (node (ref "C2") (pin "2") (pinfunction "2_2") (pintype "passive"))
      (node (ref "P1") (pin "A4") (pinfunction "VBUS_A4") (pintype "bidirectional"))
      (node (ref "P1") (pin "B4") (pinfunction "VBUS_B4") (pintype "bidirectional"))
      (node (ref "P10") (pin "1") (pinfunction "1_1") (pintype "passive"))
      (node (ref "P10") (pin "3") (pinfunction "3_3") (pintype "passive"))
      (node (ref "P9") (pin "17") (pinfunction "17_17") (pintype "passive"))
      (node (ref "U1") (pin "1") (pinfunction "AVIN_1") (pintype "power_in"))
      (node (ref "U1") (pin "10") (pinfunction "VIN_10") (pintype "power_in"))
      (node (ref "U1") (pin "9") (pinfunction "VIN_9") (pintype "power_in"))
    )
    (net (code "77") (name "VBUS_FS") (class "Default")
      (node (ref "P4") (pin "1") (pinfunction "+5V_1") (pintype "power_in"))
      (node (ref "R46") (pin "2") (pintype "passive"))
      (node (ref "U6") (pin "3") (pinfunction "VI+_3") (pintype "power_in"))
    )
    (net (code "78") (name "VBUS_HS") (class "Default")
      (node (ref "P2") (pin "1") (pinfunction "VBUS_1") (pintype "passive"))
      (node (ref "R45") (pin "2") (pintype "passive"))
      (node (ref "U5") (pin "3") (pinfunction "VI+_3") (pintype "power_in"))
    )
    (net (code "79") (name "VDD33") (class "Default")
      (node (ref "C26") (pin "1") (pinfunction "1_1") (pintype "passive"))
      (node (ref "C40") (pin "2") (pinfunction "2_2") (pintype "passive"))
      (node (ref "C42") (pin "2") (pinfunction "2_2") (pintype "passive"))
      (node (ref "P9") (pin "5") (pinfunction "5_5") (pintype "passive"))
      (node (ref "R5") (pin "1") (pintype "passive"))
      (node (ref "U2") (pin "2") (pinfunction "VDD33_2") (pintype "power_in"))
      (node (ref "U2") (pin "32") (pinfunction "VDD33_32") (pintype "power_in"))
    )
    (net (code "80") (name "VDD33A") (class "Default")
      (node (ref "C51") (pin "2") (pinfunction "2_2") (pintype "passive"))
      (node (ref "P9") (pin "3") (pinfunction "3_3") (pintype "passive"))
      (node (ref "R10") (pin "1") (pintype "passive"))
      (node (ref "U2") (pin "15") (pinfunction "VDD33A_15") (pintype "power_in"))
    )
    (net (code "81") (name "VDDIO") (class "Default")
      (node (ref "R16") (pin "1") (pintype "passive"))
      (node (ref "R18") (pin "1") (pintype "passive"))
    )
    (net (code "82") (name "VREF") (class "Default")
      (node (ref "C49") (pin "2") (pinfunction "2_2") (pintype "passive"))
      (node (ref "P9") (pin "1") (pinfunction "1_1") (pintype "passive"))
      (node (ref "R7") (pin "1") (pintype "passive"))
      (node (ref "U2") (pin "14") (pinfunction "VREFP_14") (pintype "bidirectional"))
    )
    (net (code "83") (name "unconnected-(P1-RFU1-PadA8)") (class "Default")
      (node (ref "P1") (pin "A8") (pinfunction "RFU1_A8") (pintype "bidirectional+no_connect"))
    )
    (net (code "84") (name "unconnected-(P1-RFU1-PadB8)") (class "Default")
      (node (ref "P1") (pin "B8") (pinfunction "RFU1_B8") (pintype "bidirectional+no_connect"))
    )
    (net (code "85") (name "unconnected-(U1-NC.-Pad2)") (class "Default")
      (node (ref "U1") (pin "2") (pinfunction "NC._2") (pintype "passive"))
    )
    (net (code "86") (name "unconnected-(U1-NC.-Pad3)") (class "Default")
      (node (ref "U1") (pin "3") (pinfunction "NC._3") (pintype "passive"))
    )
    (net (code "87") (name "unconnected-(U3-NC.-Pad1)") (class "Default")
      (node (ref "U3") (pin "1") (pinfunction "NC._1") (pintype "passive+no_connect"))
    )
  )
)
